# 16-POWER_MANAGEMENT.net
KiCad netlist of a schematic drawn in Altium Designer
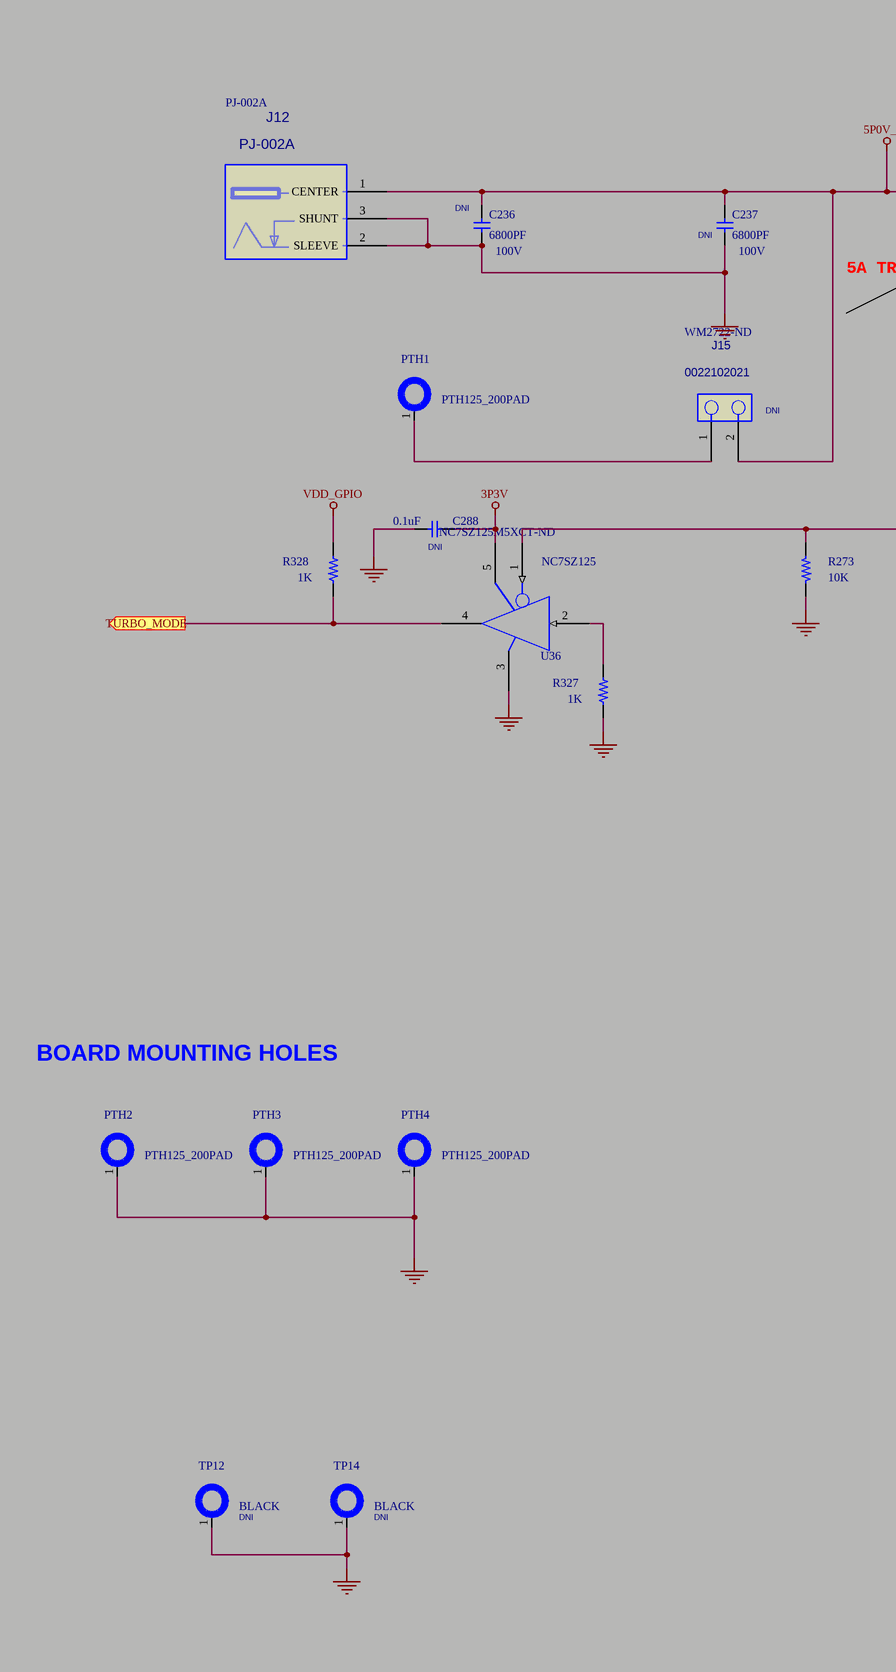
[diagram p0: 16-POWER MANAGEMENT.SchDoc, left]
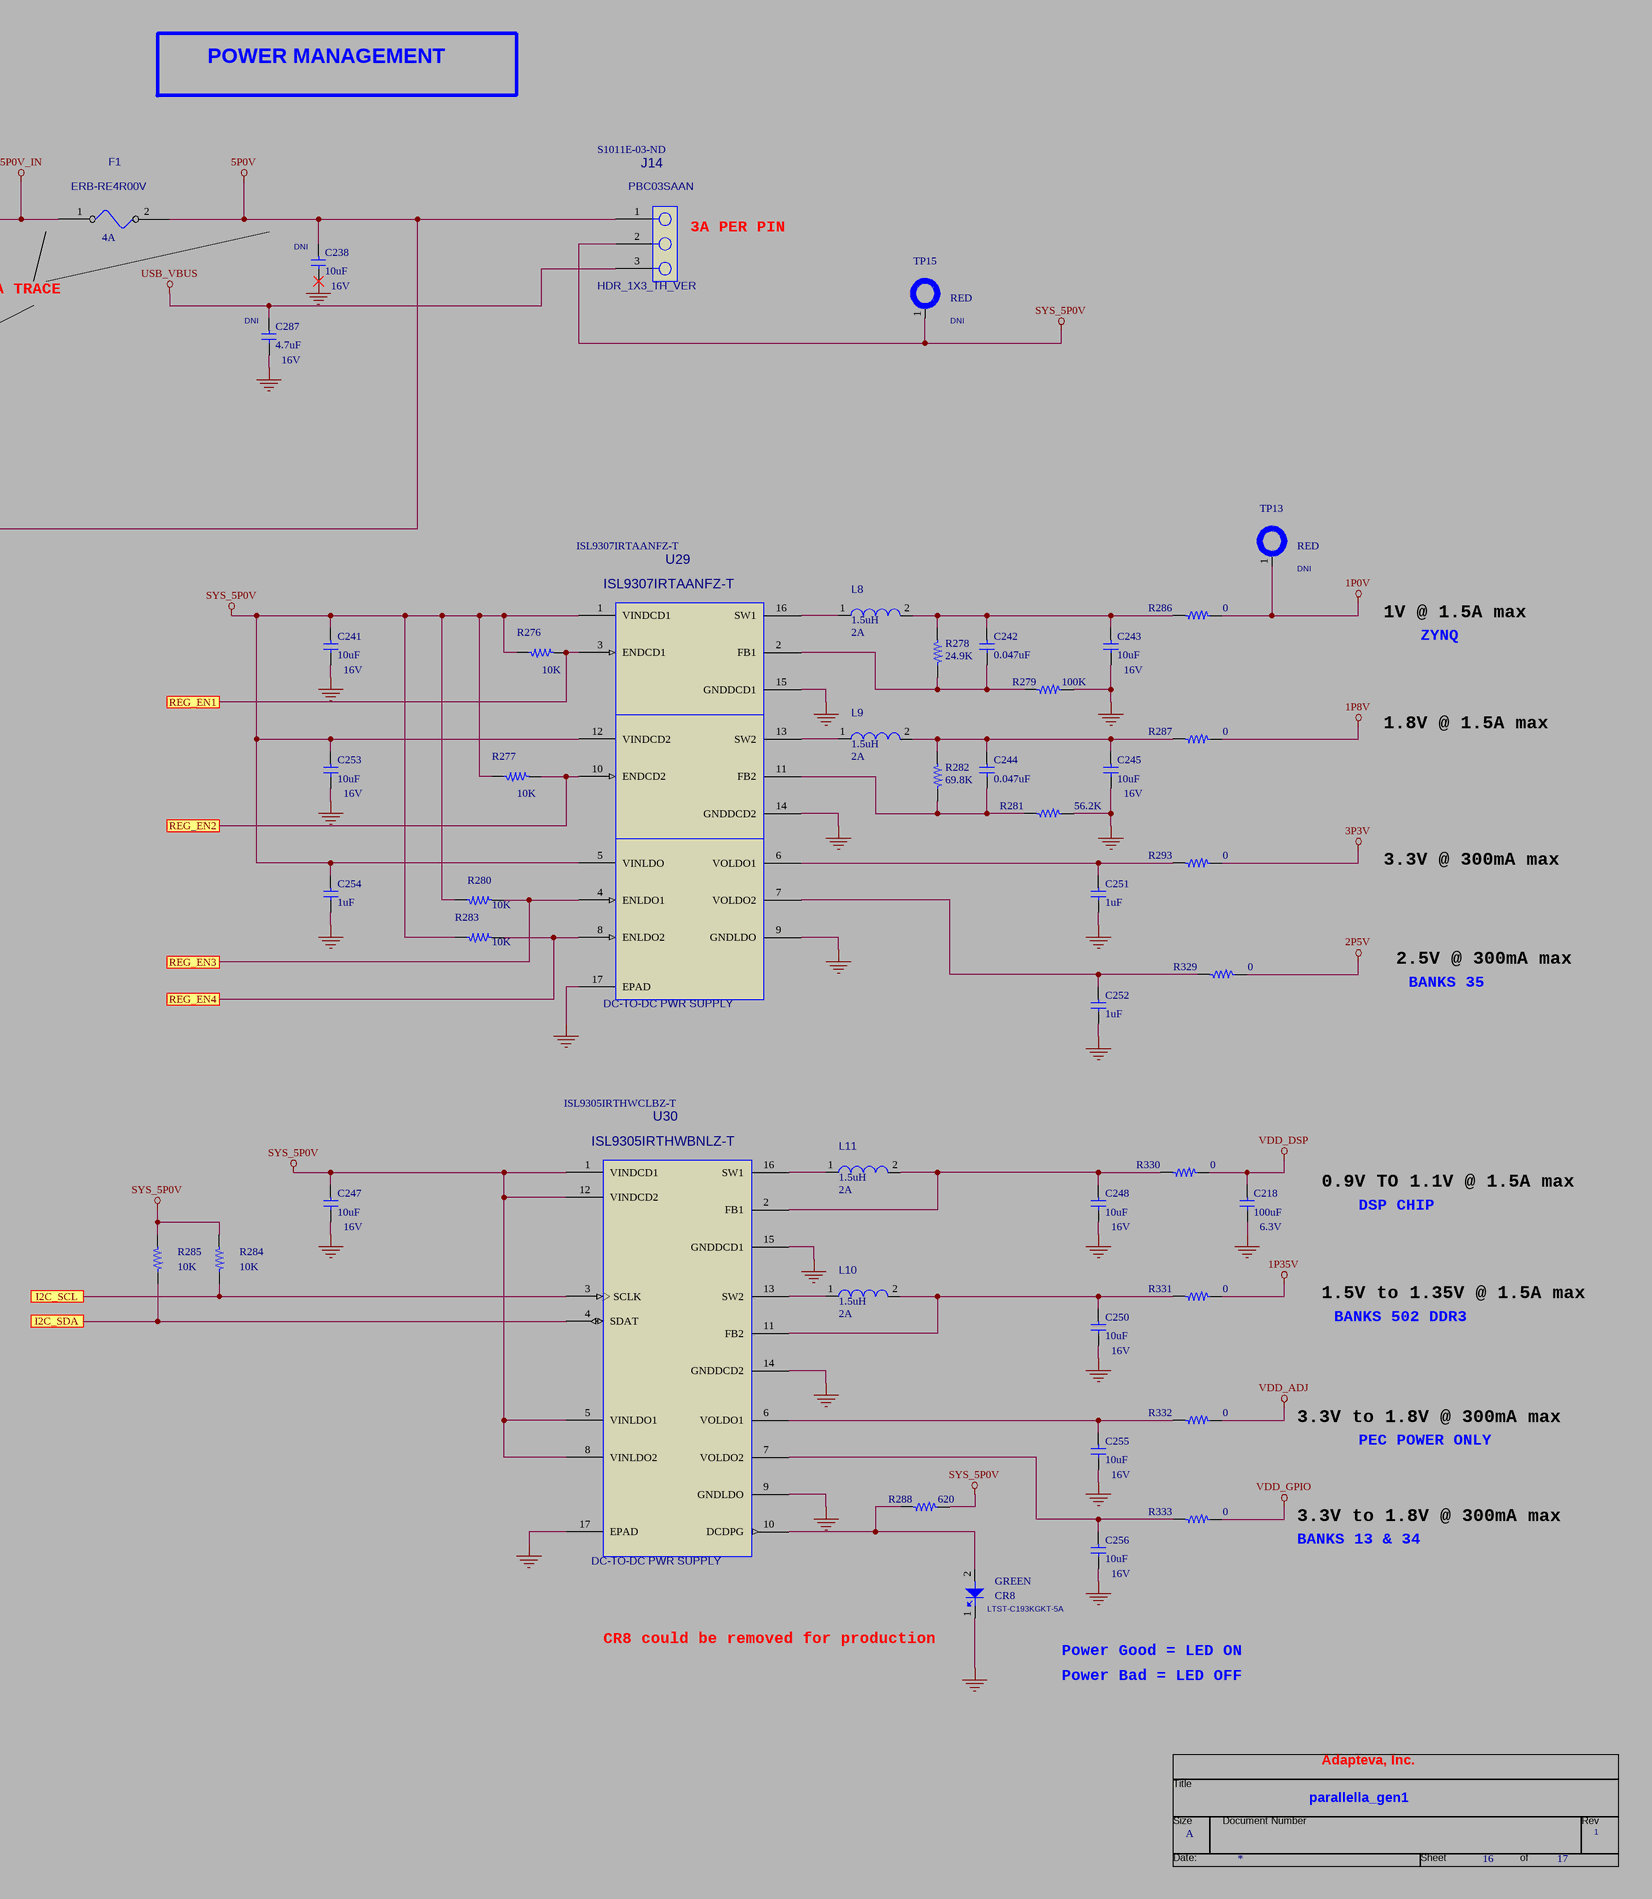
[diagram p1: 16-POWER MANAGEMENT.SchDoc, right]

(export (version "E")
  (design (tool "Eeschema 10.0.6"))
  (components
    (comp (ref "C218")
      (value "100uF")
      (footprint "C1210")
      (description "CAP, 1210, 100UF, X5R, 6.3V, LOW ESR")
      (fields
        (field (name "VOLTAGE") "6.3V")
        (field (name "MFG PART NO") "GRM32ER60J107ME20L")
        (field (name "MFG") "MURATA")
      )
      (libsource (lib "*") (part "CAP1210_100UF_X5R_LOESR"))
    )
    (comp (ref "C236")
      (value "6800PF")
      (footprint "C0805")
      (description "CAP, 0805, 6800PF, X7R, 100V")
      (fields
        (field (name "VOLTAGE") "100V")
        (field (name "MFG PART NO") "C2012X7R2A682KT5")
        (field (name "MFG") "TDK")
        (field (name "INSTALL") "DNI")
      )
      (libsource (lib "*") (part "CAP0805_6800PF_X7R"))
    )
    (comp (ref "C237")
      (value "6800PF")
      (footprint "C0805")
      (description "CAP, 0805, 6800PF, X7R, 100V")
      (fields
        (field (name "VOLTAGE") "100V")
        (field (name "MFG PART NO") "C2012X7R2A682KT5")
        (field (name "MFG") "TDK")
        (field (name "INSTALL") "DNI")
      )
      (libsource (lib "*") (part "CAP0805_6800PF_X7R"))
    )
    (comp (ref "C238")
      (value "10uF")
      (footprint "C0805")
      (description "CAP, 0805, 10UF, X5R, 16V")
      (fields
        (field (name "MFG PART NO") "C2012X5R1C106M085AC")
        (field (name "MFG") "TDK")
        (field (name "VOLTAGE") "16V")
        (field (name "INSTALL") "DNI")
      )
      (libsource (lib "*") (part "CAP0805_10UF_16V_X5R"))
    )
    (comp (ref "C241")
      (value "10uF")
      (footprint "C0805")
      (description "CAP, 0805, 10UF, X5R, 16V")
      (fields
        (field (name "MFG PART NO") "C2012X5R1C106M085AC")
        (field (name "MFG") "TDK")
        (field (name "VOLTAGE") "16V")
      )
      (libsource (lib "*") (part "CAP0805_10UF_16V_X5R"))
    )
    (comp (ref "C242")
      (value "0.047uF")
      (footprint "C0402")
      (description "CAP, 0402, 0.047UF, X5R, 25V")
      (fields (field (name "MFG") "TDK") (field (name "MFG PART NO") "C1005X5R1E473M"))
      (libsource (lib "*") (part "CAP0402_0P047UF_X5R"))
    )
    (comp (ref "C243")
      (value "10uF")
      (footprint "C0805")
      (description "CAP, 0805, 10UF, X5R, 16V")
      (fields
        (field (name "MFG PART NO") "C2012X5R1C106M085AC")
        (field (name "MFG") "TDK")
        (field (name "VOLTAGE") "16V")
      )
      (libsource (lib "*") (part "CAP0805_10UF_16V_X5R"))
    )
    (comp (ref "C244")
      (value "0.047uF")
      (footprint "C0402")
      (description "CAP, 0402, 0.047UF, X5R, 25V")
      (fields (field (name "MFG") "TDK") (field (name "MFG PART NO") "C1005X5R1E473M"))
      (libsource (lib "*") (part "CAP0402_0P047UF_X5R"))
    )
    (comp (ref "C245")
      (value "10uF")
      (footprint "C0805")
      (description "CAP, 0805, 10UF, X5R, 16V")
      (fields
        (field (name "MFG PART NO") "C2012X5R1C106M085AC")
        (field (name "MFG") "TDK")
        (field (name "VOLTAGE") "16V")
      )
      (libsource (lib "*") (part "CAP0805_10UF_16V_X5R"))
    )
    (comp (ref "C247")
      (value "10uF")
      (footprint "C0805")
      (description "CAP, 0805, 10UF, X5R, 16V")
      (fields
        (field (name "MFG PART NO") "C2012X5R1C106M085AC")
        (field (name "MFG") "TDK")
        (field (name "VOLTAGE") "16V")
      )
      (libsource (lib "*") (part "CAP0805_10UF_16V_X5R"))
    )
    (comp (ref "C248")
      (value "10uF")
      (footprint "C0805")
      (description "CAP, 0805, 10UF, X5R, 16V")
      (fields
        (field (name "MFG PART NO") "C2012X5R1C106M085AC")
        (field (name "MFG") "TDK")
        (field (name "VOLTAGE") "16V")
      )
      (libsource (lib "*") (part "CAP0805_10UF_16V_X5R"))
    )
    (comp (ref "C250")
      (value "10uF")
      (footprint "C0805")
      (description "CAP, 0805, 10UF, X5R, 16V")
      (fields
        (field (name "MFG PART NO") "C2012X5R1C106M085AC")
        (field (name "MFG") "TDK")
        (field (name "VOLTAGE") "16V")
      )
      (libsource (lib "*") (part "CAP0805_10UF_16V_X5R"))
    )
    (comp (ref "C251")
      (value "1uF")
      (footprint "C0603")
      (description "CAP, 0603, 1UF, X5R, 16V")
      (fields (field (name "MFG PART NO") "C0603C105K4PAC") (field (name "MFG") "KEMET"))
      (libsource (lib "*") (part "CAP1UF_X5R"))
    )
    (comp (ref "C252")
      (value "1uF")
      (footprint "C0603")
      (description "CAP, 0603, 1UF, X5R, 16V")
      (fields (field (name "MFG PART NO") "C0603C105K4PAC") (field (name "MFG") "KEMET"))
      (libsource (lib "*") (part "CAP1UF_X5R"))
    )
    (comp (ref "C253")
      (value "10uF")
      (footprint "C0805")
      (description "CAP, 0805, 10UF, X5R, 16V")
      (fields
        (field (name "MFG PART NO") "C2012X5R1C106M085AC")
        (field (name "MFG") "TDK")
        (field (name "VOLTAGE") "16V")
      )
      (libsource (lib "*") (part "CAP0805_10UF_16V_X5R"))
    )
    (comp (ref "C254")
      (value "1uF")
      (footprint "C0603")
      (description "CAP, 0603, 1UF, X5R, 16V")
      (fields (field (name "MFG PART NO") "C0603C105K4PAC") (field (name "MFG") "KEMET"))
      (libsource (lib "*") (part "CAP1UF_X5R"))
    )
    (comp (ref "C255")
      (value "10uF")
      (footprint "C0805")
      (description "CAP, 0805, 10UF, X5R, 16V")
      (fields
        (field (name "MFG PART NO") "C2012X5R1C106M085AC")
        (field (name "MFG") "TDK")
        (field (name "VOLTAGE") "16V")
      )
      (libsource (lib "*") (part "CAP0805_10UF_16V_X5R"))
    )
    (comp (ref "C256")
      (value "10uF")
      (footprint "C0805")
      (description "CAP, 0805, 10UF, X5R, 16V")
      (fields
        (field (name "MFG PART NO") "C2012X5R1C106M085AC")
        (field (name "MFG") "TDK")
        (field (name "VOLTAGE") "16V")
      )
      (libsource (lib "*") (part "CAP0805_10UF_16V_X5R"))
    )
    (comp (ref "C287")
      (value "4.7uF")
      (footprint "C0603")
      (description "CAP, 0603, 4.7UF, X5R, 16V")
      (fields
        (field (name "MFG") "TDK")
        (field (name "MFG PART NO") "C1608X5R1C475K080AC")
        (field (name "VOLTAGE") "16V")
        (field (name "INSTALL") "DNI")
      )
      (libsource (lib "*") (part "CAP0603_4P7UF_16V_X5R"))
    )
    (comp (ref "C288")
      (value "0.1uF")
      (footprint "C0402")
      (description "CAP, 0402, 0.1UF, X5R, 35V")
      (fields
        (field (name "MFG PART NO") "GMK105BJ104KV-F")
        (field (name "MFG") "TAIYO YUDEN")
        (field (name "INSTALL") "DNI")
      )
      (libsource (lib "*") (part "CAP0402_0P1UF_X5R_35V"))
    )
    (comp (ref "CR8")
      (value "GREEN")
      (footprint "LED_0603")
      (description "LED, 0603, 5MA, SMT, GREEN")
      (fields
        (field (name "VOLTAGE") "2V")
        (field (name "MFG") "LITE-ON INC")
        (field (name "VENDOR PN") "LTST-C193KGKT-5A")
      )
      (libsource (lib "*") (part "LED_0603_5MA_GRN"))
    )
    (comp (ref "F1")
      (value "4A")
      (footprint "F0603")
      (description "FUSE, 4A, 32V, FAST, 0603")
      (fields
        (field (name "VENDOR PN") "ERB-RE4R00V")
        (field (name "MFG PART NO") "ERB-RE4R00V")
        (field (name "MFG") "PANASONIC")
      )
      (libsource (lib "*") (part "FUSE0603_4A"))
    )
    (comp (ref "J12")
      (value "PJ-002A")
      (footprint "DC_PWR_JCK_9X14P4X11MMH")
      (description "CON, PWR, BARREL, PCB, PJ002A_TH")
      (fields (field (name "SUPPLIER PART NUMBER 1") "PJ-002A"))
      (libsource (lib "*") (part "CON_POWER_PJ002A_TH"))
    )
    (comp (ref "J14")
      (value "HDR_1X3_TH_VER")
      (footprint "HDR_1X3_TH_VER")
      (description "HDR, 1ROW, 3POS, VERT, TH, 1X3, 0.100 PITCH")
      (fields
        (field (name "VENDOR PN") "PBC03SAAN")
        (field (name "MFG") "SULLINS")
        (field (name "MFG PART NO") "PBC36SAAN")
        (field (name "SUPPLIER PART NUMBER 1") "S1011E-03-ND")
      )
      (libsource (lib "*") (part "HDR_1X3_TH_VER_0.1P"))
    )
    (comp (ref "J15")
      (value "HDR_1X2_TH_VER")
      (footprint "HDR_1X2_TH_VER")
      (description "HDR, 1ROW, 2POS, VERT, TH, 1X2")
      (fields
        (field (name "MFG PART NO") "0022102021")
        (field (name "MFG") "MOLEX")
        (field (name "VENDOR PN") "0022102021")
        (field (name "INSTALL") "DNI")
        (field (name "SUPPLIER PART NUMBER 1") "WM2722-ND")
      )
      (libsource (lib "*") (part "HDR_1X2_TH_VER"))
    )
    (comp (ref "L8")
      (value "1.5uH")
      (footprint "IND2_2X2P5X1P2MMH")
      (description "IND, 1.5uH, 2A")
      (fields
        (field (name "MFG") "TDK")
        (field (name "MFG PART NO") "VLS252012ET-1R5N")
        (field (name "CURRENT") "2A")
      )
      (libsource (lib "*") (part "IND_1P5UH_2A"))
    )
    (comp (ref "L9")
      (value "1.5uH")
      (footprint "IND2_2X2P5X1P2MMH")
      (description "IND, 1.5uH, 2A")
      (fields
        (field (name "MFG") "TDK")
        (field (name "MFG PART NO") "VLS252012ET-1R5N")
        (field (name "CURRENT") "2A")
      )
      (libsource (lib "*") (part "IND_1P5UH_2A"))
    )
    (comp (ref "L10")
      (value "1.5uH")
      (footprint "IND2_2X2P5X1P2MMH")
      (description "IND, 1.5uH, 2A")
      (fields
        (field (name "MFG") "TDK")
        (field (name "MFG PART NO") "VLS252012ET-1R5N")
        (field (name "CURRENT") "2A")
      )
      (libsource (lib "*") (part "IND_1P5UH_2A"))
    )
    (comp (ref "L11")
      (value "1.5uH")
      (footprint "IND2_2X2P5X1P2MMH")
      (description "IND, 1.5uH, 2A")
      (fields
        (field (name "MFG") "TDK")
        (field (name "MFG PART NO") "VLS252012ET-1R5N")
        (field (name "CURRENT") "2A")
      )
      (libsource (lib "*") (part "IND_1P5UH_2A"))
    )
    (comp (ref "PTH1")
      (value "PTH125_200PAD")
      (footprint "PTH125_200PAD")
      (libsource (lib "*") (part "PTH125_200PAD"))
    )
    (comp (ref "PTH2")
      (value "PTH125_200PAD")
      (footprint "PTH125_200PAD")
      (libsource (lib "*") (part "PTH125_200PAD"))
    )
    (comp (ref "PTH3")
      (value "PTH125_200PAD")
      (footprint "PTH125_200PAD")
      (libsource (lib "*") (part "PTH125_200PAD"))
    )
    (comp (ref "PTH4")
      (value "PTH125_200PAD")
      (footprint "PTH125_200PAD")
      (libsource (lib "*") (part "PTH125_200PAD"))
    )
    (comp (ref "R273")
      (value "10K")
      (footprint "R0402")
      (description "RES, 0402, 10K")
      (fields (field (name "MFG") "VISHAY") (field (name "MFG PART NO") "CRCW040210K0FKED"))
      (libsource (lib "*") (part "RES0402_10K"))
    )
    (comp (ref "R276")
      (value "10K")
      (footprint "R0402")
      (description "RES, 0402, 10K")
      (fields (field (name "MFG") "VISHAY") (field (name "MFG PART NO") "CRCW040210K0FKED"))
      (libsource (lib "*") (part "RES0402_10K"))
    )
    (comp (ref "R277")
      (value "10K")
      (footprint "R0402")
      (description "RES, 0402, 10K")
      (fields (field (name "MFG") "VISHAY") (field (name "MFG PART NO") "CRCW040210K0FKED"))
      (libsource (lib "*") (part "RES0402_10K"))
    )
    (comp (ref "R278")
      (value "24.9K")
      (footprint "R0603")
      (description "RES, 0603, 24.9K")
      (fields (field (name "MFG PART NO") "CRCW060324K9FKEA") (field (name "MFG") "VISHAY/DALE"))
      (libsource (lib "*") (part "RES0603_24K9"))
    )
    (comp (ref "R279")
      (value "100K")
      (footprint "R0603")
      (description "RES, 0603, 100K")
      (fields (field (name "MFG") "VISHAY/DALE") (field (name "MFG PART NO") "CRCW0603100KFKEA"))
      (libsource (lib "*") (part "RES0603_100K"))
    )
    (comp (ref "R280")
      (value "10K")
      (footprint "R0402")
      (description "RES, 0402, 10K")
      (fields (field (name "MFG") "VISHAY") (field (name "MFG PART NO") "CRCW040210K0FKED"))
      (libsource (lib "*") (part "RES0402_10K"))
    )
    (comp (ref "R281")
      (value "56.2K")
      (footprint "R0402")
      (description "RES, 0402, 56.2K")
      (fields (field (name "MFG PART NO") "CRCW040256K2FKED") (field (name "MFG") "VISHAY"))
      (libsource (lib "*") (part "RES0402_56K2"))
    )
    (comp (ref "R282")
      (value "69.8K")
      (footprint "R0603")
      (description "RES, 0603, 69.8K")
      (fields (field (name "MFG") "VISHAY") (field (name "MFG PART NO") "CRCW060369K8FKEA"))
      (libsource (lib "*") (part "RES0603_69K8"))
    )
    (comp (ref "R283")
      (value "10K")
      (footprint "R0402")
      (description "RES, 0402, 10K")
      (fields (field (name "MFG") "VISHAY") (field (name "MFG PART NO") "CRCW040210K0FKED"))
      (libsource (lib "*") (part "RES0402_10K"))
    )
    (comp (ref "R284")
      (value "10K")
      (footprint "R0402")
      (description "RES, 0402, 10K")
      (fields (field (name "MFG") "VISHAY") (field (name "MFG PART NO") "CRCW040210K0FKED"))
      (libsource (lib "*") (part "RES0402_10K"))
    )
    (comp (ref "R285")
      (value "10K")
      (footprint "R0402")
      (description "RES, 0402, 10K")
      (fields (field (name "MFG") "VISHAY") (field (name "MFG PART NO") "CRCW040210K0FKED"))
      (libsource (lib "*") (part "RES0402_10K"))
    )
    (comp (ref "R286")
      (value "0")
      (footprint "R0402")
      (description "RES, 0402, 0 OHM, 1%")
      (fields (field (name "MFG") "VISHAY") (field (name "MFG PART NO") "CRCW04020000Z0ED"))
      (libsource (lib "*") (part "RES0402_0"))
    )
    (comp (ref "R287")
      (value "0")
      (footprint "R0402")
      (description "RES, 0402, 0 OHM, 1%")
      (fields (field (name "MFG") "VISHAY") (field (name "MFG PART NO") "CRCW04020000Z0ED"))
      (libsource (lib "*") (part "RES0402_0"))
    )
    (comp (ref "R288")
      (value "620")
      (footprint "R0402")
      (description "RES, 0402, 620, 1%")
      (fields (field (name "MFG") "VISHAY") (field (name "MFG PART NO") "CRCW0402620RFKED"))
      (libsource (lib "*") (part "RES0402_620"))
    )
    (comp (ref "R293")
      (value "0")
      (footprint "R0402")
      (description "RES, 0402, 0 OHM, 1%")
      (fields (field (name "MFG") "VISHAY") (field (name "MFG PART NO") "CRCW04020000Z0ED"))
      (libsource (lib "*") (part "RES0402_0"))
    )
    (comp (ref "R327")
      (value "1K")
      (footprint "R0402")
      (description "RES, 0402, 1K")
      (fields (field (name "MFG") "VISHAY") (field (name "MFG PART NO") "CRCW04021K00FKED"))
      (libsource (lib "*") (part "RES0402_1K"))
    )
    (comp (ref "R328")
      (value "1K")
      (footprint "R0402")
      (description "RES, 0402, 1K")
      (fields (field (name "MFG") "VISHAY") (field (name "MFG PART NO") "CRCW04021K00FKED"))
      (libsource (lib "*") (part "RES0402_1K"))
    )
    (comp (ref "R329")
      (value "0")
      (footprint "R0402")
      (description "RES, 0402, 0 OHM, 1%")
      (fields (field (name "MFG") "VISHAY") (field (name "MFG PART NO") "CRCW04020000Z0ED"))
      (libsource (lib "*") (part "RES0402_0"))
    )
    (comp (ref "R330")
      (value "0")
      (footprint "R0402")
      (description "RES, 0402, 0 OHM, 1%")
      (fields (field (name "MFG") "VISHAY") (field (name "MFG PART NO") "CRCW04020000Z0ED"))
      (libsource (lib "*") (part "RES0402_0"))
    )
    (comp (ref "R331")
      (value "0")
      (footprint "R0402")
      (description "RES, 0402, 0 OHM, 1%")
      (fields (field (name "MFG") "VISHAY") (field (name "MFG PART NO") "CRCW04020000Z0ED"))
      (libsource (lib "*") (part "RES0402_0"))
    )
    (comp (ref "R332")
      (value "0")
      (footprint "R0402")
      (description "RES, 0402, 0 OHM, 1%")
      (fields (field (name "MFG") "VISHAY") (field (name "MFG PART NO") "CRCW04020000Z0ED"))
      (libsource (lib "*") (part "RES0402_0"))
    )
    (comp (ref "R333")
      (value "0")
      (footprint "R0402")
      (description "RES, 0402, 0 OHM, 1%")
      (fields (field (name "MFG") "VISHAY") (field (name "MFG PART NO") "CRCW04020000Z0ED"))
      (libsource (lib "*") (part "RES0402_0"))
    )
    (comp (ref "TP12")
      (value "BLACK")
      (footprint "TP55")
      (description "PC Test Point Miniature")
      (fields
        (field (name "MFG") "KEYSTONE")
        (field (name "MFG PART NO") "5001")
        (field (name "INSTALL") "DNI")
      )
      (libsource (lib "*") (part "TEST_TERM_BLK"))
    )
    (comp (ref "TP13")
      (value "RED")
      (footprint "TP55")
      (description "PC TEST POINT MINIATURE")
      (fields
        (field (name "MFG PART NO") "5000")
        (field (name "MFG") "KEYSTONE")
        (field (name "INSTALL") "DNI")
      )
      (libsource (lib "*") (part "TEST_TERM_RED"))
    )
    (comp (ref "TP14")
      (value "BLACK")
      (footprint "TP55")
      (description "PC Test Point Miniature")
      (fields
        (field (name "MFG") "KEYSTONE")
        (field (name "MFG PART NO") "5001")
        (field (name "INSTALL") "DNI")
      )
      (libsource (lib "*") (part "TEST_TERM_BLK"))
    )
    (comp (ref "TP15")
      (value "RED")
      (footprint "TP55")
      (description "PC TEST POINT MINIATURE")
      (fields
        (field (name "MFG PART NO") "5000")
        (field (name "MFG") "KEYSTONE")
        (field (name "INSTALL") "DNI")
      )
      (libsource (lib "*") (part "TEST_TERM_RED"))
    )
    (comp (ref "U29")
      (value "DC-TO-DC PWR SUPPLY")
      (footprint "TQFN16_4SQXP75H_P65P")
      (description "IC, dual step-down converters + dual LDOs, TQFN16")
      (fields
        (field (name "MFG PART NO") "ISL9307IRTAANFZ-T")
        (field (name "MFG") "INTERSIL")
        (field (name "VENDOR PN") "ISL9307IRTAANFZ-T")
        (field (name "SUPPLIER PART NUMBER 1") "ISL9307IRTAANFZ-T")
      )
      (libsource (lib "*") (part "IC_ISL9307_DCDC_CONV"))
    )
    (comp (ref "U30")
      (value "DC-TO-DC PWR SUPPLY")
      (footprint "TQFN16_4SQXP75H_P65P")
      (description "IC, dual step-down converters + dual LDOs, I2C interface, TQFN16")
      (fields
        (field (name "MFG PART NO") "ISL9305IRTHWCLBZ-T")
        (field (name "MFG") "INTERSIL")
        (field (name "VENDOR PN") "ISL9305IRTHWBNLZ-T")
        (field (name "SUPPLIER PART NUMBER 1") "ISL9305IRTHWCLBZ-T")
      )
      (libsource (lib "*") (part "IC_ISL9305_DCDC_CONV"))
    )
    (comp (ref "U36")
      (value "NC7SZ125")
      (footprint "SOT_5PIN")
      (fields
        (field (name "PART_NUMBER") "XXX-XXXXX-XX")
        (field (name "MFG") "FAIRCHILD")
        (field (name "MFG PART NO") "NC7SZ125M5X")
        (field (name "SUPPLIER PART NUMBER 1") "NC7SZ125M5XCT-ND")
      )
      (libsource (lib "*") (part "NC7SZ125"))
    )
  )
  (nets
    (net (code "1") (name "/I2C_SCL") (class "Default")
      (node (ref "R284") (pin "2") (pinfunction "2_2") (pintype "passive"))
      (node (ref "U30") (pin "3") (pinfunction "SCLK_3") (pintype "input"))
    )
    (net (code "2") (name "/I2C_SDA") (class "Default")
      (node (ref "R285") (pin "2") (pinfunction "2_2") (pintype "passive"))
      (node (ref "U30") (pin "4") (pinfunction "SDAT_4") (pintype "bidirectional"))
    )
    (net (code "3") (name "/REG_EN1") (class "Default")
      (node (ref "R276") (pin "1") (pinfunction "1_1") (pintype "passive"))
      (node (ref "U29") (pin "3") (pinfunction "ENDCD1_3") (pintype "input"))
    )
    (net (code "4") (name "/REG_EN2") (class "Default")
      (node (ref "R277") (pin "1") (pinfunction "1_1") (pintype "passive"))
      (node (ref "U29") (pin "10") (pinfunction "ENDCD2_10") (pintype "input"))
    )
    (net (code "5") (name "/REG_EN3") (class "Default")
      (node (ref "R280") (pin "1") (pinfunction "1_1") (pintype "passive"))
      (node (ref "U29") (pin "4") (pinfunction "ENLDO1_4") (pintype "input"))
    )
    (net (code "6") (name "/REG_EN4") (class "Default")
      (node (ref "R283") (pin "1") (pinfunction "1_1") (pintype "passive"))
      (node (ref "U29") (pin "8") (pinfunction "ENLDO2_8") (pintype "input"))
    )
    (net (code "7") (name "/TURBO_MODE") (class "Default")
      (node (ref "R328") (pin "2") (pinfunction "2_2") (pintype "passive"))
      (node (ref "U36") (pin "4") (pinfunction "Y_4") (pintype "tri_state"))
    )
    (net (code "8") (name "1P0V") (class "Default")
      (node (ref "R286") (pin "2") (pinfunction "2_2") (pintype "passive"))
      (node (ref "TP13") (pin "1") (pinfunction "1_1") (pintype "passive"))
    )
    (net (code "9") (name "1P8V") (class "Default")
      (node (ref "R287") (pin "2") (pinfunction "2_2") (pintype "passive"))
    )
    (net (code "10") (name "1P35V") (class "Default")
      (node (ref "R331") (pin "2") (pinfunction "2_2") (pintype "passive"))
    )
    (net (code "11") (name "2P5V") (class "Default")
      (node (ref "R329") (pin "2") (pinfunction "2_2") (pintype "passive"))
    )
    (net (code "12") (name "3P3V") (class "Default")
      (node (ref "C288") (pin "2") (pinfunction "2_2") (pintype "passive"))
      (node (ref "R293") (pin "2") (pinfunction "2_2") (pintype "passive"))
      (node (ref "U36") (pin "5") (pinfunction "VCC_5") (pintype "passive"))
    )
    (net (code "13") (name "5P0V") (class "Default")
      (node (ref "C238") (pin "1") (pinfunction "1_1") (pintype "passive"))
      (node (ref "F1") (pin "2") (pinfunction "2_2") (pintype "passive"))
      (node (ref "J14") (pin "1") (pinfunction "1_1") (pintype "passive"))
      (node (ref "R273") (pin "1") (pinfunction "1_1") (pintype "passive"))
      (node (ref "U36") (pin "1") (pinfunction "~{OE}_1") (pintype "input"))
    )
    (net (code "14") (name "5P0V_IN") (class "Default")
      (node (ref "C236") (pin "1") (pinfunction "1_1") (pintype "passive"))
      (node (ref "C237") (pin "1") (pinfunction "1_1") (pintype "passive"))
      (node (ref "F1") (pin "1") (pinfunction "1_1") (pintype "passive"))
      (node (ref "J12") (pin "1") (pinfunction "CENTER_1") (pintype "passive"))
      (node (ref "J15") (pin "2") (pinfunction "2_2") (pintype "passive"))
    )
    (net (code "15") (name "GND") (class "Default")
      (node (ref "C218") (pin "2") (pinfunction "2_2") (pintype "passive"))
      (node (ref "C236") (pin "2") (pinfunction "2_2") (pintype "passive"))
      (node (ref "C237") (pin "2") (pinfunction "2_2") (pintype "passive"))
      (node (ref "C238") (pin "2") (pinfunction "2_2") (pintype "passive"))
      (node (ref "C241") (pin "2") (pinfunction "2_2") (pintype "passive"))
      (node (ref "C243") (pin "2") (pinfunction "2_2") (pintype "passive"))
      (node (ref "C245") (pin "2") (pinfunction "2_2") (pintype "passive"))
      (node (ref "C247") (pin "2") (pinfunction "2_2") (pintype "passive"))
      (node (ref "C248") (pin "2") (pinfunction "2_2") (pintype "passive"))
      (node (ref "C250") (pin "2") (pinfunction "2_2") (pintype "passive"))
      (node (ref "C251") (pin "2") (pinfunction "2_2") (pintype "passive"))
      (node (ref "C252") (pin "2") (pinfunction "2_2") (pintype "passive"))
      (node (ref "C253") (pin "2") (pinfunction "2_2") (pintype "passive"))
      (node (ref "C254") (pin "2") (pinfunction "2_2") (pintype "passive"))
      (node (ref "C255") (pin "2") (pinfunction "2_2") (pintype "passive"))
      (node (ref "C256") (pin "2") (pinfunction "2_2") (pintype "passive"))
      (node (ref "C287") (pin "2") (pinfunction "2_2") (pintype "passive"))
      (node (ref "C288") (pin "1") (pinfunction "1_1") (pintype "passive"))
      (node (ref "CR8") (pin "1") (pinfunction "C_1") (pintype "passive"))
      (node (ref "J12") (pin "2") (pinfunction "SLEEVE_2") (pintype "passive"))
      (node (ref "J12") (pin "3") (pinfunction "SHUNT_3") (pintype "passive"))
      (node (ref "PTH2") (pin "1") (pinfunction "1_1") (pintype "passive"))
      (node (ref "PTH3") (pin "1") (pinfunction "1_1") (pintype "passive"))
      (node (ref "PTH4") (pin "1") (pinfunction "1_1") (pintype "passive"))
      (node (ref "R273") (pin "2") (pinfunction "2_2") (pintype "passive"))
      (node (ref "R279") (pin "2") (pinfunction "2_2") (pintype "passive"))
      (node (ref "R281") (pin "2") (pinfunction "2_2") (pintype "passive"))
      (node (ref "R327") (pin "2") (pinfunction "2_2") (pintype "passive"))
      (node (ref "TP12") (pin "1") (pinfunction "1_1") (pintype "passive"))
      (node (ref "TP14") (pin "1") (pinfunction "1_1") (pintype "passive"))
      (node (ref "U29") (pin "14") (pinfunction "GNDDCD2_14") (pintype "power_in"))
      (node (ref "U29") (pin "15") (pinfunction "GNDDCD1_15") (pintype "power_in"))
      (node (ref "U29") (pin "17") (pinfunction "EPAD_17") (pintype "passive"))
      (node (ref "U29") (pin "9") (pinfunction "GNDLDO_9") (pintype "power_in"))
      (node (ref "U30") (pin "14") (pinfunction "GNDDCD2_14") (pintype "power_in"))
      (node (ref "U30") (pin "15") (pinfunction "GNDDCD1_15") (pintype "power_in"))
      (node (ref "U30") (pin "17") (pinfunction "EPAD_17") (pintype "passive"))
      (node (ref "U30") (pin "9") (pinfunction "GNDLDO_9") (pintype "power_in"))
      (node (ref "U36") (pin "3") (pinfunction "GND_3") (pintype "passive"))
    )
    (net (code "16") (name "Net-(C242-Pad1)") (class "Default")
      (node (ref "C242") (pin "1") (pinfunction "1_1") (pintype "passive"))
      (node (ref "C243") (pin "1") (pinfunction "1_1") (pintype "passive"))
      (node (ref "L8") (pin "2") (pinfunction "2_2") (pintype "passive"))
      (node (ref "R278") (pin "1") (pinfunction "1_1") (pintype "passive"))
      (node (ref "R286") (pin "1") (pinfunction "1_1") (pintype "passive"))
    )
    (net (code "17") (name "Net-(C244-Pad1)") (class "Default")
      (node (ref "C244") (pin "1") (pinfunction "1_1") (pintype "passive"))
      (node (ref "C245") (pin "1") (pinfunction "1_1") (pintype "passive"))
      (node (ref "L9") (pin "2") (pinfunction "2_2") (pintype "passive"))
      (node (ref "R282") (pin "1") (pinfunction "1_1") (pintype "passive"))
      (node (ref "R287") (pin "1") (pinfunction "1_1") (pintype "passive"))
    )
    (net (code "18") (name "Net-(CR8-A)") (class "Default")
      (node (ref "CR8") (pin "2") (pinfunction "A_2") (pintype "passive"))
      (node (ref "R288") (pin "1") (pinfunction "1_1") (pintype "passive"))
      (node (ref "U30") (pin "10") (pinfunction "DCDPG_10") (pintype "output"))
    )
    (net (code "19") (name "Net-(J15-Pad1)") (class "Default")
      (node (ref "J15") (pin "1") (pinfunction "1_1") (pintype "passive"))
      (node (ref "PTH1") (pin "1") (pinfunction "1_1") (pintype "passive"))
    )
    (net (code "20") (name "Net-(U29-FB1)") (class "Default")
      (node (ref "C242") (pin "2") (pinfunction "2_2") (pintype "passive"))
      (node (ref "R278") (pin "2") (pinfunction "2_2") (pintype "passive"))
      (node (ref "R279") (pin "1") (pinfunction "1_1") (pintype "passive"))
      (node (ref "U29") (pin "2") (pinfunction "FB1_2") (pintype "passive"))
    )
    (net (code "21") (name "Net-(U29-FB2)") (class "Default")
      (node (ref "C244") (pin "2") (pinfunction "2_2") (pintype "passive"))
      (node (ref "R281") (pin "1") (pinfunction "1_1") (pintype "passive"))
      (node (ref "R282") (pin "2") (pinfunction "2_2") (pintype "passive"))
      (node (ref "U29") (pin "11") (pinfunction "FB2_11") (pintype "passive"))
    )
    (net (code "22") (name "Net-(U29-SW1)") (class "Default")
      (node (ref "L8") (pin "1") (pinfunction "1_1") (pintype "passive"))
      (node (ref "U29") (pin "16") (pinfunction "SW1_16") (pintype "passive"))
    )
    (net (code "23") (name "Net-(U29-SW2)") (class "Default")
      (node (ref "L9") (pin "1") (pinfunction "1_1") (pintype "passive"))
      (node (ref "U29") (pin "13") (pinfunction "SW2_13") (pintype "passive"))
    )
    (net (code "24") (name "Net-(U29-VOLDO1)") (class "Default")
      (node (ref "C251") (pin "1") (pinfunction "1_1") (pintype "passive"))
      (node (ref "R293") (pin "1") (pinfunction "1_1") (pintype "passive"))
      (node (ref "U29") (pin "6") (pinfunction "VOLDO1_6") (pintype "passive"))
    )
    (net (code "25") (name "Net-(U29-VOLDO2)") (class "Default")
      (node (ref "C252") (pin "1") (pinfunction "1_1") (pintype "passive"))
      (node (ref "R329") (pin "1") (pinfunction "1_1") (pintype "passive"))
      (node (ref "U29") (pin "7") (pinfunction "VOLDO2_7") (pintype "passive"))
    )
    (net (code "26") (name "Net-(U30-FB1)") (class "Default")
      (node (ref "C248") (pin "1") (pinfunction "1_1") (pintype "passive"))
      (node (ref "L11") (pin "2") (pinfunction "2_2") (pintype "passive"))
      (node (ref "R330") (pin "1") (pinfunction "1_1") (pintype "passive"))
      (node (ref "U30") (pin "2") (pinfunction "FB1_2") (pintype "passive"))
    )
    (net (code "27") (name "Net-(U30-FB2)") (class "Default")
      (node (ref "C250") (pin "1") (pinfunction "1_1") (pintype "passive"))
      (node (ref "L10") (pin "2") (pinfunction "2_2") (pintype "passive"))
      (node (ref "R331") (pin "1") (pinfunction "1_1") (pintype "passive"))
      (node (ref "U30") (pin "11") (pinfunction "FB2_11") (pintype "passive"))
    )
    (net (code "28") (name "Net-(U30-SW1)") (class "Default")
      (node (ref "L11") (pin "1") (pinfunction "1_1") (pintype "passive"))
      (node (ref "U30") (pin "16") (pinfunction "SW1_16") (pintype "passive"))
    )
    (net (code "29") (name "Net-(U30-SW2)") (class "Default")
      (node (ref "L10") (pin "1") (pinfunction "1_1") (pintype "passive"))
      (node (ref "U30") (pin "13") (pinfunction "SW2_13") (pintype "passive"))
    )
    (net (code "30") (name "Net-(U30-VOLDO1)") (class "Default")
      (node (ref "C255") (pin "1") (pinfunction "1_1") (pintype "passive"))
      (node (ref "R332") (pin "1") (pinfunction "1_1") (pintype "passive"))
      (node (ref "U30") (pin "6") (pinfunction "VOLDO1_6") (pintype "passive"))
    )
    (net (code "31") (name "Net-(U30-VOLDO2)") (class "Default")
      (node (ref "C256") (pin "1") (pinfunction "1_1") (pintype "passive"))
      (node (ref "R333") (pin "1") (pinfunction "1_1") (pintype "passive"))
      (node (ref "U30") (pin "7") (pinfunction "VOLDO2_7") (pintype "passive"))
    )
    (net (code "32") (name "Net-(U36-A)") (class "Default")
      (node (ref "R327") (pin "1") (pinfunction "1_1") (pintype "passive"))
      (node (ref "U36") (pin "2") (pinfunction "A_2") (pintype "input"))
    )
    (net (code "33") (name "SYS_5P0V") (class "Default")
      (node (ref "C241") (pin "1") (pinfunction "1_1") (pintype "passive"))
      (node (ref "C247") (pin "1") (pinfunction "1_1") (pintype "passive"))
      (node (ref "C253") (pin "1") (pinfunction "1_1") (pintype "passive"))
      (node (ref "C254") (pin "1") (pinfunction "1_1") (pintype "passive"))
      (node (ref "J14") (pin "2") (pinfunction "2_2") (pintype "passive"))
      (node (ref "R276") (pin "2") (pinfunction "2_2") (pintype "passive"))
      (node (ref "R277") (pin "2") (pinfunction "2_2") (pintype "passive"))
      (node (ref "R280") (pin "2") (pinfunction "2_2") (pintype "passive"))
      (node (ref "R283") (pin "2") (pinfunction "2_2") (pintype "passive"))
      (node (ref "R284") (pin "1") (pinfunction "1_1") (pintype "passive"))
      (node (ref "R285") (pin "1") (pinfunction "1_1") (pintype "passive"))
      (node (ref "R288") (pin "2") (pinfunction "2_2") (pintype "passive"))
      (node (ref "TP15") (pin "1") (pinfunction "1_1") (pintype "passive"))
      (node (ref "U29") (pin "1") (pinfunction "VINDCD1_1") (pintype "passive"))
      (node (ref "U29") (pin "12") (pinfunction "VINDCD2_12") (pintype "passive"))
      (node (ref "U29") (pin "5") (pinfunction "VINLDO_5") (pintype "passive"))
      (node (ref "U30") (pin "1") (pinfunction "VINDCD1_1") (pintype "passive"))
      (node (ref "U30") (pin "12") (pinfunction "VINDCD2_12") (pintype "passive"))
      (node (ref "U30") (pin "5") (pinfunction "VINLDO1_5") (pintype "passive"))
      (node (ref "U30") (pin "8") (pinfunction "VINLDO2_8") (pintype "passive"))
    )
    (net (code "34") (name "USB_VBUS") (class "Default")
      (node (ref "C287") (pin "1") (pinfunction "1_1") (pintype "passive"))
      (node (ref "J14") (pin "3") (pinfunction "3_3") (pintype "passive"))
    )
    (net (code "35") (name "VDD_ADJ") (class "Default")
      (node (ref "R332") (pin "2") (pinfunction "2_2") (pintype "passive"))
    )
    (net (code "36") (name "VDD_DSP") (class "Default")
      (node (ref "C218") (pin "1") (pinfunction "1_1") (pintype "passive"))
      (node (ref "R330") (pin "2") (pinfunction "2_2") (pintype "passive"))
    )
    (net (code "37") (name "VDD_GPIO") (class "Default")
      (node (ref "R328") (pin "1") (pinfunction "1_1") (pintype "passive"))
      (node (ref "R333") (pin "2") (pinfunction "2_2") (pintype "passive"))
    )
  )
)
